# INA219x4_DoubleWing.net
KiCad netlist of a schematic drawn in EAGLE
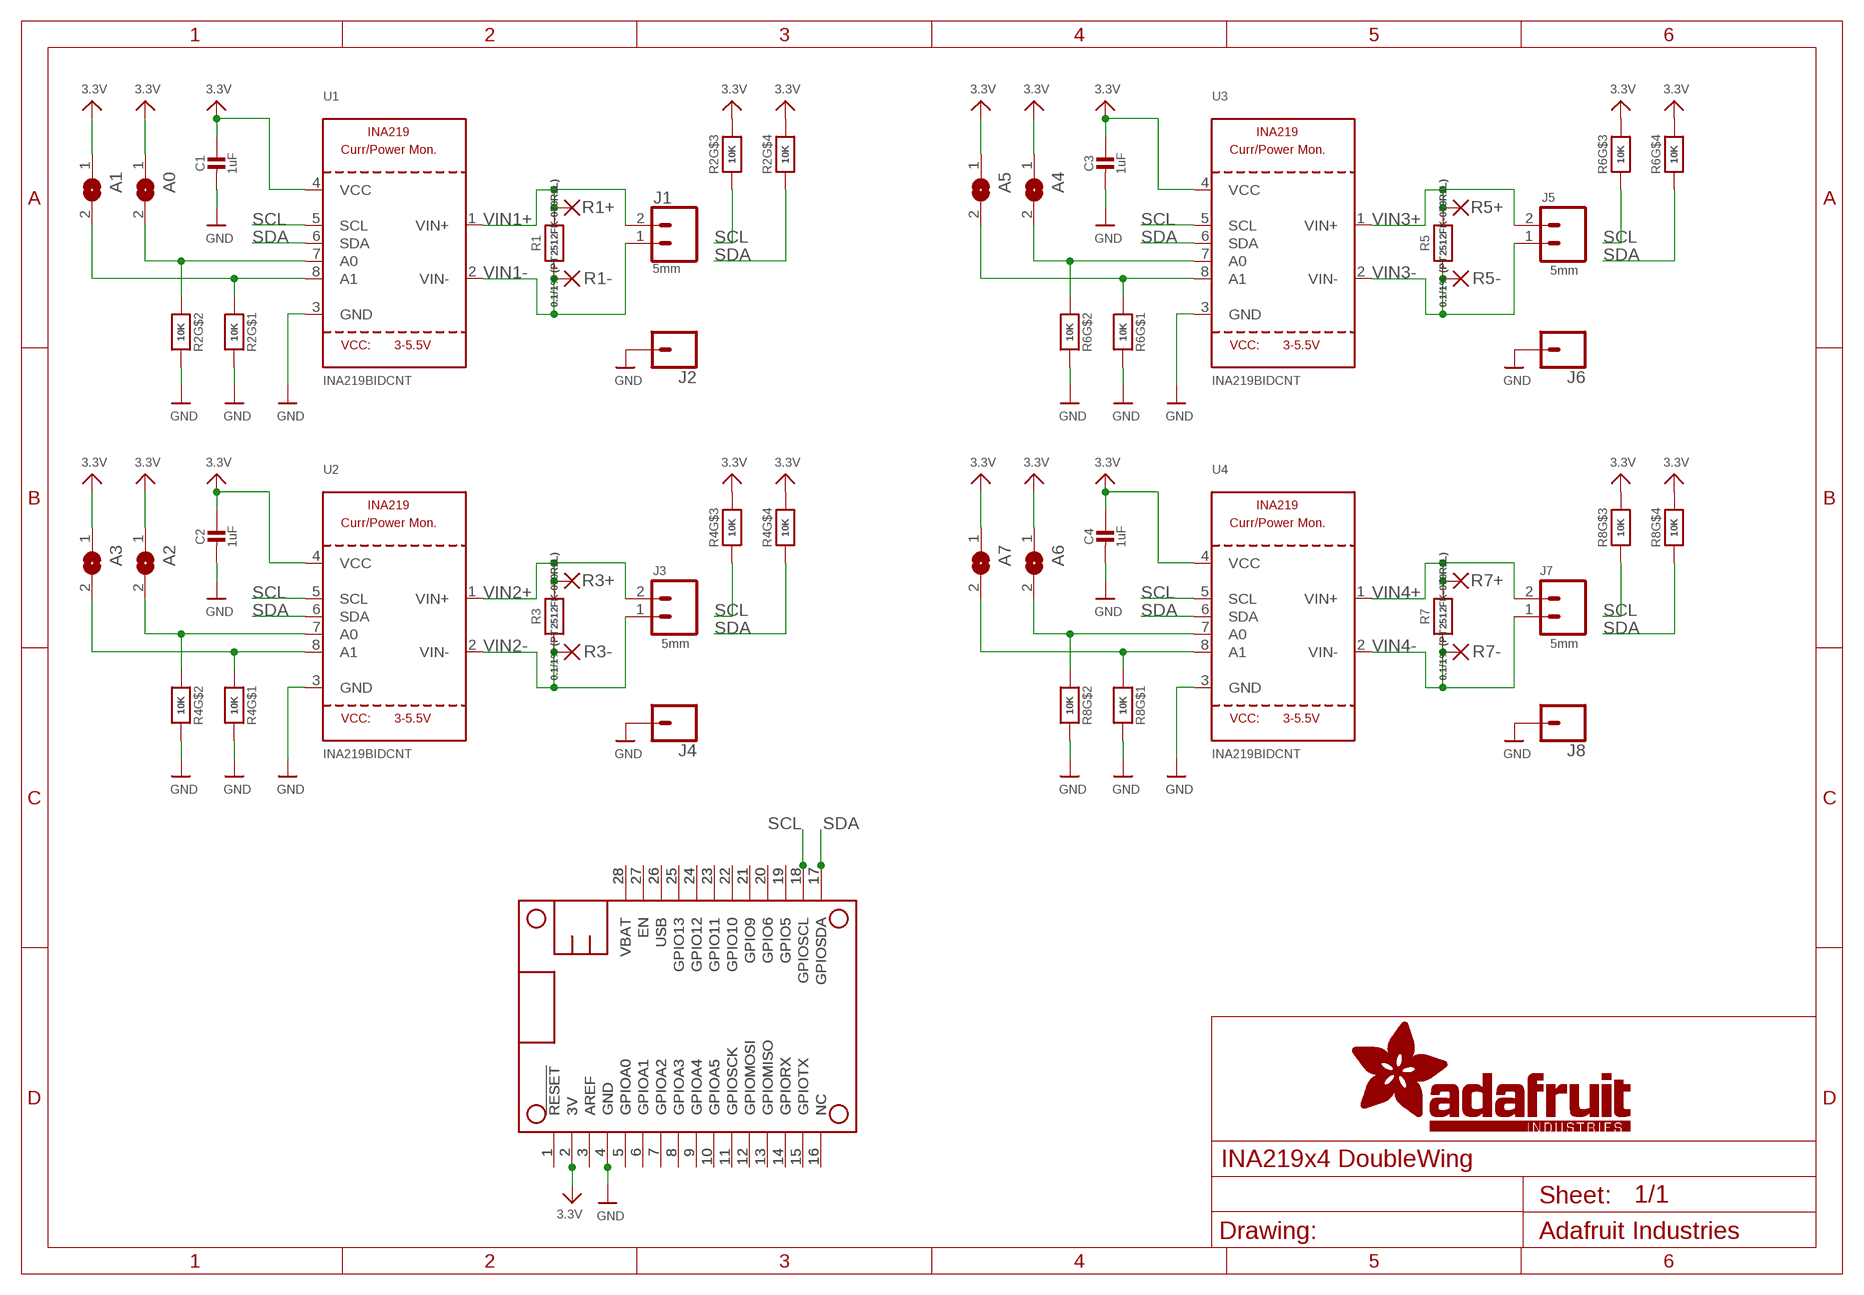
[diagram p0: schematic, sheet 1]

(export (version "E")
  (design (tool "Eeschema 10.0.6"))
  (components
    (comp (ref "A0")
      (value "SOLDERJUMPERREFLOW_NOPASTE")
      (footprint "eagle-import:SOLDERJUMPER_REFLOW_NOPASTE")
      (libsource (lib "eagle-import") (part "SOLDERJUMPERREFLOW_NOPASTE"))
    )
    (comp (ref "A1")
      (value "SOLDERJUMPERREFLOW_NOPASTE")
      (footprint "eagle-import:SOLDERJUMPER_REFLOW_NOPASTE")
      (libsource (lib "eagle-import") (part "SOLDERJUMPERREFLOW_NOPASTE"))
    )
    (comp (ref "A2")
      (value "SOLDERJUMPERREFLOW_NOPASTE")
      (footprint "eagle-import:SOLDERJUMPER_REFLOW_NOPASTE")
      (libsource (lib "eagle-import") (part "SOLDERJUMPERREFLOW_NOPASTE"))
    )
    (comp (ref "A3")
      (value "SOLDERJUMPERREFLOW_NOPASTE")
      (footprint "eagle-import:SOLDERJUMPER_REFLOW_NOPASTE")
      (libsource (lib "eagle-import") (part "SOLDERJUMPERREFLOW_NOPASTE"))
    )
    (comp (ref "A4")
      (value "SOLDERJUMPERREFLOW_NOPASTE")
      (footprint "eagle-import:SOLDERJUMPER_REFLOW_NOPASTE")
      (libsource (lib "eagle-import") (part "SOLDERJUMPERREFLOW_NOPASTE"))
    )
    (comp (ref "A5")
      (value "SOLDERJUMPERREFLOW_NOPASTE")
      (footprint "eagle-import:SOLDERJUMPER_REFLOW_NOPASTE")
      (libsource (lib "eagle-import") (part "SOLDERJUMPERREFLOW_NOPASTE"))
    )
    (comp (ref "A6")
      (value "SOLDERJUMPERREFLOW_NOPASTE")
      (footprint "eagle-import:SOLDERJUMPER_REFLOW_NOPASTE")
      (libsource (lib "eagle-import") (part "SOLDERJUMPERREFLOW_NOPASTE"))
    )
    (comp (ref "A7")
      (value "SOLDERJUMPERREFLOW_NOPASTE")
      (footprint "eagle-import:SOLDERJUMPER_REFLOW_NOPASTE")
      (libsource (lib "eagle-import") (part "SOLDERJUMPERREFLOW_NOPASTE"))
    )
    (comp (ref "C1")
      (value "1uF")
      (footprint "eagle-import:0805-NO@1")
      (libsource (lib "eagle-import") (part "CAP_CERAMIC0805-NOOUTLINE"))
    )
    (comp (ref "C2")
      (value "1uF")
      (footprint "eagle-import:0805-NO@1")
      (libsource (lib "eagle-import") (part "CAP_CERAMIC0805-NOOUTLINE"))
    )
    (comp (ref "C3")
      (value "1uF")
      (footprint "eagle-import:0805-NO@1")
      (libsource (lib "eagle-import") (part "CAP_CERAMIC0805-NOOUTLINE"))
    )
    (comp (ref "C4")
      (value "1uF")
      (footprint "eagle-import:0805-NO@1")
      (libsource (lib "eagle-import") (part "CAP_CERAMIC0805-NOOUTLINE"))
    )
    (comp (ref "J1")
      (value "5mm")
      (footprint "eagle-import:SCREWTERMINAL-5MM-2")
      (libsource (lib "eagle-import") (part "CONN_025MM"))
    )
    (comp (ref "J2")
      (value "CONN_01")
      (footprint "eagle-import:1X01")
      (libsource (lib "eagle-import") (part "CONN_01"))
    )
    (comp (ref "J3")
      (value "5mm")
      (footprint "eagle-import:SCREWTERMINAL-5MM-2")
      (libsource (lib "eagle-import") (part "CONN_025MM"))
    )
    (comp (ref "J4")
      (value "CONN_01")
      (footprint "eagle-import:1X01")
      (libsource (lib "eagle-import") (part "CONN_01"))
    )
    (comp (ref "J5")
      (value "5mm")
      (footprint "eagle-import:SCREWTERMINAL-5MM-2")
      (libsource (lib "eagle-import") (part "CONN_025MM"))
    )
    (comp (ref "J6")
      (value "CONN_01")
      (footprint "eagle-import:1X01")
      (libsource (lib "eagle-import") (part "CONN_01"))
    )
    (comp (ref "J7")
      (value "5mm")
      (footprint "eagle-import:SCREWTERMINAL-5MM-2")
      (libsource (lib "eagle-import") (part "CONN_025MM"))
    )
    (comp (ref "J8")
      (value "CONN_01")
      (footprint "eagle-import:1X01")
      (libsource (lib "eagle-import") (part "CONN_01"))
    )
    (comp (ref "MS1")
      (value "FEATHERWING_NODIM")
      (footprint "eagle-import:FEATHERWING_DIM")
      (libsource (lib "eagle-import") (part "FEATHERWING_NODIM"))
    )
    (comp (ref "MS2")
      (value "FEATHERWING_NODIM")
      (footprint "eagle-import:FEATHERWING_DIM")
      (libsource (lib "eagle-import") (part "FEATHERWING_NODIM"))
    )
    (comp (ref "R1")
      (value "0.1/1% (PT2512FK-070R1L)")
      (footprint "eagle-import:2512")
      (libsource (lib "eagle-import") (part "RESISTOR2512"))
    )
    (comp (ref "R1+")
      (value "1,6/0,9")
      (footprint "eagle-import:1,6_0,9")
      (libsource (lib "eagle-import") (part "1,6/0,9"))
    )
    (comp (ref "R1-")
      (value "1,6/0,9")
      (footprint "eagle-import:1,6_0,9")
      (libsource (lib "eagle-import") (part "1,6/0,9"))
    )
    (comp (ref "R2")
      (value "10K")
      (footprint "eagle-import:RESPACK_4X0603")
      (libsource (lib "eagle-import") (part "RESISTOR_4PACK"))
    )
    (comp (ref "R3")
      (value "0.1/1% (PT2512FK-070R1L)")
      (footprint "eagle-import:2512")
      (libsource (lib "eagle-import") (part "RESISTOR2512"))
    )
    (comp (ref "R3+")
      (value "1,6/0,9")
      (footprint "eagle-import:1,6_0,9")
      (libsource (lib "eagle-import") (part "1,6/0,9"))
    )
    (comp (ref "R3-")
      (value "1,6/0,9")
      (footprint "eagle-import:1,6_0,9")
      (libsource (lib "eagle-import") (part "1,6/0,9"))
    )
    (comp (ref "R4")
      (value "10K")
      (footprint "eagle-import:RESPACK_4X0603")
      (libsource (lib "eagle-import") (part "RESISTOR_4PACK"))
    )
    (comp (ref "R5")
      (value "0.1/1% (PT2512FK-070R1L)")
      (footprint "eagle-import:2512")
      (libsource (lib "eagle-import") (part "RESISTOR2512"))
    )
    (comp (ref "R5+")
      (value "1,6/0,9")
      (footprint "eagle-import:1,6_0,9")
      (libsource (lib "eagle-import") (part "1,6/0,9"))
    )
    (comp (ref "R5-")
      (value "1,6/0,9")
      (footprint "eagle-import:1,6_0,9")
      (libsource (lib "eagle-import") (part "1,6/0,9"))
    )
    (comp (ref "R6")
      (value "10K")
      (footprint "eagle-import:RESPACK_4X0603")
      (libsource (lib "eagle-import") (part "RESISTOR_4PACK"))
    )
    (comp (ref "R7")
      (value "0.1/1% (PT2512FK-070R1L)")
      (footprint "eagle-import:2512")
      (libsource (lib "eagle-import") (part "RESISTOR2512"))
    )
    (comp (ref "R7+")
      (value "1,6/0,9")
      (footprint "eagle-import:1,6_0,9")
      (libsource (lib "eagle-import") (part "1,6/0,9"))
    )
    (comp (ref "R7-")
      (value "1,6/0,9")
      (footprint "eagle-import:1,6_0,9")
      (libsource (lib "eagle-import") (part "1,6/0,9"))
    )
    (comp (ref "R8")
      (value "10K")
      (footprint "eagle-import:RESPACK_4X0603")
      (libsource (lib "eagle-import") (part "RESISTOR_4PACK"))
    )
    (comp (ref "U1")
      (value "INA219BIDCNT")
      (footprint "eagle-import:SOT23-8")
      (libsource (lib "eagle-import") (part "INA219"))
    )
    (comp (ref "U2")
      (value "INA219BIDCNT")
      (footprint "eagle-import:SOT23-8")
      (libsource (lib "eagle-import") (part "INA219"))
    )
    (comp (ref "U3")
      (value "INA219BIDCNT")
      (footprint "eagle-import:SOT23-8")
      (libsource (lib "eagle-import") (part "INA219"))
    )
    (comp (ref "U4")
      (value "INA219BIDCNT")
      (footprint "eagle-import:SOT23-8")
      (libsource (lib "eagle-import") (part "INA219"))
    )
  )
  (nets
    (net (code "1") (name "/SCL") (class "Default")
      (node (ref "MS1") (pin "18") (pinfunction "GPIOSCL_18") (pintype "bidirectional"))
      (node (ref "MS2") (pin "18") (pinfunction "GPIOSCL_18") (pintype "bidirectional"))
      (node (ref "R2") (pin "3") (pinfunction "1_3") (pintype "passive"))
      (node (ref "R4") (pin "3") (pinfunction "1_3") (pintype "passive"))
      (node (ref "R6") (pin "3") (pinfunction "1_3") (pintype "passive"))
      (node (ref "R8") (pin "3") (pinfunction "1_3") (pintype "passive"))
      (node (ref "U1") (pin "5") (pinfunction "SCL_5") (pintype "bidirectional"))
      (node (ref "U2") (pin "5") (pinfunction "SCL_5") (pintype "bidirectional"))
      (node (ref "U3") (pin "5") (pinfunction "SCL_5") (pintype "bidirectional"))
      (node (ref "U4") (pin "5") (pinfunction "SCL_5") (pintype "bidirectional"))
    )
    (net (code "2") (name "/SDA") (class "Default")
      (node (ref "MS1") (pin "17") (pinfunction "GPIOSDA_17") (pintype "bidirectional"))
      (node (ref "MS2") (pin "17") (pinfunction "GPIOSDA_17") (pintype "bidirectional"))
      (node (ref "R2") (pin "4") (pinfunction "1_4") (pintype "passive"))
      (node (ref "R4") (pin "4") (pinfunction "1_4") (pintype "passive"))
      (node (ref "R6") (pin "4") (pinfunction "1_4") (pintype "passive"))
      (node (ref "R8") (pin "4") (pinfunction "1_4") (pintype "passive"))
      (node (ref "U1") (pin "6") (pinfunction "SDA_6") (pintype "bidirectional"))
      (node (ref "U2") (pin "6") (pinfunction "SDA_6") (pintype "bidirectional"))
      (node (ref "U3") (pin "6") (pinfunction "SDA_6") (pintype "bidirectional"))
      (node (ref "U4") (pin "6") (pinfunction "SDA_6") (pintype "bidirectional"))
    )
    (net (code "3") (name "/VIN1+") (class "Default")
      (node (ref "J1") (pin "2") (pinfunction "2_2") (pintype "passive"))
      (node (ref "R1") (pin "2") (pinfunction "2_2") (pintype "passive"))
      (node (ref "R1+") (pin "1") (pinfunction "P_1") (pintype "passive"))
      (node (ref "U1") (pin "1") (pinfunction "VIN+_1") (pintype "bidirectional"))
    )
    (net (code "4") (name "/VIN1-") (class "Default")
      (node (ref "J1") (pin "1") (pinfunction "1_1") (pintype "passive"))
      (node (ref "R1") (pin "1") (pinfunction "1_1") (pintype "passive"))
      (node (ref "R1-") (pin "1") (pinfunction "P_1") (pintype "passive"))
      (node (ref "U1") (pin "2") (pinfunction "VIN-_2") (pintype "bidirectional"))
    )
    (net (code "5") (name "/VIN2+") (class "Default")
      (node (ref "J3") (pin "2") (pinfunction "2_2") (pintype "passive"))
      (node (ref "R3") (pin "2") (pinfunction "2_2") (pintype "passive"))
      (node (ref "R3+") (pin "1") (pinfunction "P_1") (pintype "passive"))
      (node (ref "U2") (pin "1") (pinfunction "VIN+_1") (pintype "bidirectional"))
    )
    (net (code "6") (name "/VIN2-") (class "Default")
      (node (ref "J3") (pin "1") (pinfunction "1_1") (pintype "passive"))
      (node (ref "R3") (pin "1") (pinfunction "1_1") (pintype "passive"))
      (node (ref "R3-") (pin "1") (pinfunction "P_1") (pintype "passive"))
      (node (ref "U2") (pin "2") (pinfunction "VIN-_2") (pintype "bidirectional"))
    )
    (net (code "7") (name "/VIN3+") (class "Default")
      (node (ref "J5") (pin "2") (pinfunction "2_2") (pintype "passive"))
      (node (ref "R5") (pin "2") (pinfunction "2_2") (pintype "passive"))
      (node (ref "R5+") (pin "1") (pinfunction "P_1") (pintype "passive"))
      (node (ref "U3") (pin "1") (pinfunction "VIN+_1") (pintype "bidirectional"))
    )
    (net (code "8") (name "/VIN3-") (class "Default")
      (node (ref "J5") (pin "1") (pinfunction "1_1") (pintype "passive"))
      (node (ref "R5") (pin "1") (pinfunction "1_1") (pintype "passive"))
      (node (ref "R5-") (pin "1") (pinfunction "P_1") (pintype "passive"))
      (node (ref "U3") (pin "2") (pinfunction "VIN-_2") (pintype "bidirectional"))
    )
    (net (code "9") (name "/VIN4+") (class "Default")
      (node (ref "J7") (pin "2") (pinfunction "2_2") (pintype "passive"))
      (node (ref "R7") (pin "2") (pinfunction "2_2") (pintype "passive"))
      (node (ref "R7+") (pin "1") (pinfunction "P_1") (pintype "passive"))
      (node (ref "U4") (pin "1") (pinfunction "VIN+_1") (pintype "bidirectional"))
    )
    (net (code "10") (name "/VIN4-") (class "Default")
      (node (ref "J7") (pin "1") (pinfunction "1_1") (pintype "passive"))
      (node (ref "R7") (pin "1") (pinfunction "1_1") (pintype "passive"))
      (node (ref "R7-") (pin "1") (pinfunction "P_1") (pintype "passive"))
      (node (ref "U4") (pin "2") (pinfunction "VIN-_2") (pintype "bidirectional"))
    )
    (net (code "11") (name "3.3V") (class "Default")
      (node (ref "A0") (pin "1") (pinfunction "1_1") (pintype "passive"))
      (node (ref "A1") (pin "1") (pinfunction "1_1") (pintype "passive"))
      (node (ref "A2") (pin "1") (pinfunction "1_1") (pintype "passive"))
      (node (ref "A3") (pin "1") (pinfunction "1_1") (pintype "passive"))
      (node (ref "A4") (pin "1") (pinfunction "1_1") (pintype "passive"))
      (node (ref "A5") (pin "1") (pinfunction "1_1") (pintype "passive"))
      (node (ref "A6") (pin "1") (pinfunction "1_1") (pintype "passive"))
      (node (ref "A7") (pin "1") (pinfunction "1_1") (pintype "passive"))
      (node (ref "C1") (pin "1") (pinfunction "1_1") (pintype "passive"))
      (node (ref "C2") (pin "1") (pinfunction "1_1") (pintype "passive"))
      (node (ref "C3") (pin "1") (pinfunction "1_1") (pintype "passive"))
      (node (ref "C4") (pin "1") (pinfunction "1_1") (pintype "passive"))
      (node (ref "MS1") (pin "2") (pinfunction "3V_2") (pintype "power_in"))
      (node (ref "MS2") (pin "2") (pinfunction "3V_2") (pintype "power_in"))
      (node (ref "R2") (pin "5") (pinfunction "2_5") (pintype "passive"))
      (node (ref "R2") (pin "6") (pinfunction "2_6") (pintype "passive"))
      (node (ref "R4") (pin "5") (pinfunction "2_5") (pintype "passive"))
      (node (ref "R4") (pin "6") (pinfunction "2_6") (pintype "passive"))
      (node (ref "R6") (pin "5") (pinfunction "2_5") (pintype "passive"))
      (node (ref "R6") (pin "6") (pinfunction "2_6") (pintype "passive"))
      (node (ref "R8") (pin "5") (pinfunction "2_5") (pintype "passive"))
      (node (ref "R8") (pin "6") (pinfunction "2_6") (pintype "passive"))
      (node (ref "U1") (pin "4") (pinfunction "VCC_4") (pintype "power_in"))
      (node (ref "U2") (pin "4") (pinfunction "VCC_4") (pintype "power_in"))
      (node (ref "U3") (pin "4") (pinfunction "VCC_4") (pintype "power_in"))
      (node (ref "U4") (pin "4") (pinfunction "VCC_4") (pintype "power_in"))
    )
    (net (code "12") (name "GND") (class "Default")
      (node (ref "C1") (pin "2") (pinfunction "2_2") (pintype "passive"))
      (node (ref "C2") (pin "2") (pinfunction "2_2") (pintype "passive"))
      (node (ref "C3") (pin "2") (pinfunction "2_2") (pintype "passive"))
      (node (ref "C4") (pin "2") (pinfunction "2_2") (pintype "passive"))
      (node (ref "J2") (pin "1") (pinfunction "1_1") (pintype "passive"))
      (node (ref "J4") (pin "1") (pinfunction "1_1") (pintype "passive"))
      (node (ref "J6") (pin "1") (pinfunction "1_1") (pintype "passive"))
      (node (ref "J8") (pin "1") (pinfunction "1_1") (pintype "passive"))
      (node (ref "MS1") (pin "4") (pinfunction "GND_4") (pintype "power_in"))
      (node (ref "MS2") (pin "4") (pinfunction "GND_4") (pintype "power_in"))
      (node (ref "R2") (pin "7") (pinfunction "2_7") (pintype "passive"))
      (node (ref "R2") (pin "8") (pinfunction "2_8") (pintype "passive"))
      (node (ref "R4") (pin "7") (pinfunction "2_7") (pintype "passive"))
      (node (ref "R4") (pin "8") (pinfunction "2_8") (pintype "passive"))
      (node (ref "R6") (pin "7") (pinfunction "2_7") (pintype "passive"))
      (node (ref "R6") (pin "8") (pinfunction "2_8") (pintype "passive"))
      (node (ref "R8") (pin "7") (pinfunction "2_7") (pintype "passive"))
      (node (ref "R8") (pin "8") (pinfunction "2_8") (pintype "passive"))
      (node (ref "U1") (pin "3") (pinfunction "GND_3") (pintype "power_in"))
      (node (ref "U2") (pin "3") (pinfunction "GND_3") (pintype "power_in"))
      (node (ref "U3") (pin "3") (pinfunction "GND_3") (pintype "power_in"))
      (node (ref "U4") (pin "3") (pinfunction "GND_3") (pintype "power_in"))
    )
    (net (code "13") (name "Net-(MS1-AREF)") (class "Default")
      (node (ref "MS1") (pin "3") (pinfunction "AREF_3") (pintype "passive"))
      (node (ref "MS2") (pin "3") (pinfunction "AREF_3") (pintype "passive"))
    )
    (net (code "14") (name "Net-(MS1-EN)") (class "Default")
      (node (ref "MS1") (pin "27") (pinfunction "EN_27") (pintype "passive"))
      (node (ref "MS2") (pin "27") (pinfunction "EN_27") (pintype "passive"))
    )
    (net (code "15") (name "Net-(MS1-GPIO5)") (class "Default")
      (node (ref "MS1") (pin "19") (pinfunction "GPIO5_19") (pintype "bidirectional"))
      (node (ref "MS2") (pin "19") (pinfunction "GPIO5_19") (pintype "bidirectional"))
    )
    (net (code "16") (name "Net-(MS1-GPIO6)") (class "Default")
      (node (ref "MS1") (pin "20") (pinfunction "GPIO6_20") (pintype "bidirectional"))
      (node (ref "MS2") (pin "20") (pinfunction "GPIO6_20") (pintype "bidirectional"))
    )
    (net (code "17") (name "Net-(MS1-GPIO9)") (class "Default")
      (node (ref "MS1") (pin "21") (pinfunction "GPIO9_21") (pintype "bidirectional"))
      (node (ref "MS2") (pin "21") (pinfunction "GPIO9_21") (pintype "bidirectional"))
    )
    (net (code "18") (name "Net-(MS1-GPIO10)") (class "Default")
      (node (ref "MS1") (pin "22") (pinfunction "GPIO10_22") (pintype "bidirectional"))
      (node (ref "MS2") (pin "22") (pinfunction "GPIO10_22") (pintype "bidirectional"))
    )
    (net (code "19") (name "Net-(MS1-GPIO11)") (class "Default")
      (node (ref "MS1") (pin "23") (pinfunction "GPIO11_23") (pintype "bidirectional"))
      (node (ref "MS2") (pin "23") (pinfunction "GPIO11_23") (pintype "bidirectional"))
    )
    (net (code "20") (name "Net-(MS1-GPIO12)") (class "Default")
      (node (ref "MS1") (pin "24") (pinfunction "GPIO12_24") (pintype "bidirectional"))
      (node (ref "MS2") (pin "24") (pinfunction "GPIO12_24") (pintype "bidirectional"))
    )
    (net (code "21") (name "Net-(MS1-GPIO13)") (class "Default")
      (node (ref "MS1") (pin "25") (pinfunction "GPIO13_25") (pintype "bidirectional"))
      (node (ref "MS2") (pin "25") (pinfunction "GPIO13_25") (pintype "bidirectional"))
    )
    (net (code "22") (name "Net-(MS1-GPIOA0)") (class "Default")
      (node (ref "MS1") (pin "5") (pinfunction "GPIOA0_5") (pintype "bidirectional"))
      (node (ref "MS2") (pin "5") (pinfunction "GPIOA0_5") (pintype "bidirectional"))
    )
    (net (code "23") (name "Net-(MS1-GPIOA1)") (class "Default")
      (node (ref "MS1") (pin "6") (pinfunction "GPIOA1_6") (pintype "bidirectional"))
      (node (ref "MS2") (pin "6") (pinfunction "GPIOA1_6") (pintype "bidirectional"))
    )
    (net (code "24") (name "Net-(MS1-GPIOA2)") (class "Default")
      (node (ref "MS1") (pin "7") (pinfunction "GPIOA2_7") (pintype "bidirectional"))
      (node (ref "MS2") (pin "7") (pinfunction "GPIOA2_7") (pintype "bidirectional"))
    )
    (net (code "25") (name "Net-(MS1-GPIOA3)") (class "Default")
      (node (ref "MS1") (pin "8") (pinfunction "GPIOA3_8") (pintype "bidirectional"))
      (node (ref "MS2") (pin "8") (pinfunction "GPIOA3_8") (pintype "bidirectional"))
    )
    (net (code "26") (name "Net-(MS1-GPIOA4)") (class "Default")
      (node (ref "MS1") (pin "9") (pinfunction "GPIOA4_9") (pintype "bidirectional"))
      (node (ref "MS2") (pin "9") (pinfunction "GPIOA4_9") (pintype "bidirectional"))
    )
    (net (code "27") (name "Net-(MS1-GPIOA5)") (class "Default")
      (node (ref "MS1") (pin "10") (pinfunction "GPIOA5_10") (pintype "bidirectional"))
      (node (ref "MS2") (pin "10") (pinfunction "GPIOA5_10") (pintype "bidirectional"))
    )
    (net (code "28") (name "Net-(MS1-GPIOMISO)") (class "Default")
      (node (ref "MS1") (pin "13") (pinfunction "GPIOMISO_13") (pintype "bidirectional"))
      (node (ref "MS2") (pin "13") (pinfunction "GPIOMISO_13") (pintype "bidirectional"))
    )
    (net (code "29") (name "Net-(MS1-GPIOMOSI)") (class "Default")
      (node (ref "MS1") (pin "12") (pinfunction "GPIOMOSI_12") (pintype "bidirectional"))
      (node (ref "MS2") (pin "12") (pinfunction "GPIOMOSI_12") (pintype "bidirectional"))
    )
    (net (code "30") (name "Net-(MS1-GPIORX)") (class "Default")
      (node (ref "MS1") (pin "14") (pinfunction "GPIORX_14") (pintype "bidirectional"))
      (node (ref "MS2") (pin "14") (pinfunction "GPIORX_14") (pintype "bidirectional"))
    )
    (net (code "31") (name "Net-(MS1-GPIOSCK)") (class "Default")
      (node (ref "MS1") (pin "11") (pinfunction "GPIOSCK_11") (pintype "bidirectional"))
      (node (ref "MS2") (pin "11") (pinfunction "GPIOSCK_11") (pintype "bidirectional"))
    )
    (net (code "32") (name "Net-(MS1-GPIOTX)") (class "Default")
      (node (ref "MS1") (pin "15") (pinfunction "GPIOTX_15") (pintype "bidirectional"))
      (node (ref "MS2") (pin "15") (pinfunction "GPIOTX_15") (pintype "bidirectional"))
    )
    (net (code "33") (name "Net-(MS1-NC)") (class "Default")
      (node (ref "MS1") (pin "16") (pinfunction "NC_16") (pintype "passive"))
      (node (ref "MS2") (pin "16") (pinfunction "NC_16") (pintype "passive"))
    )
    (net (code "34") (name "Net-(MS1-USB)") (class "Default")
      (node (ref "MS1") (pin "26") (pinfunction "USB_26") (pintype "power_in"))
      (node (ref "MS2") (pin "26") (pinfunction "USB_26") (pintype "power_in"))
    )
    (net (code "35") (name "Net-(MS1-VBAT)") (class "Default")
      (node (ref "MS1") (pin "28") (pinfunction "VBAT_28") (pintype "power_in"))
      (node (ref "MS2") (pin "28") (pinfunction "VBAT_28") (pintype "power_in"))
    )
    (net (code "36") (name "Net-(MS1-~{RESET})") (class "Default")
      (node (ref "MS1") (pin "1") (pinfunction "~{RESET}_1") (pintype "input"))
      (node (ref "MS2") (pin "1") (pinfunction "~{RESET}_1") (pintype "input"))
    )
    (net (code "37") (name "Net-(R2B-1)") (class "Default")
      (node (ref "A0") (pin "2") (pinfunction "2_2") (pintype "passive"))
      (node (ref "R2") (pin "2") (pinfunction "1_2") (pintype "passive"))
      (node (ref "U1") (pin "7") (pinfunction "A0_7") (pintype "bidirectional"))
    )
    (net (code "38") (name "Net-(R4B-1)") (class "Default")
      (node (ref "A2") (pin "2") (pinfunction "2_2") (pintype "passive"))
      (node (ref "R4") (pin "2") (pinfunction "1_2") (pintype "passive"))
      (node (ref "U2") (pin "7") (pinfunction "A0_7") (pintype "bidirectional"))
    )
    (net (code "39") (name "Net-(R6B-1)") (class "Default")
      (node (ref "A4") (pin "2") (pinfunction "2_2") (pintype "passive"))
      (node (ref "R6") (pin "2") (pinfunction "1_2") (pintype "passive"))
      (node (ref "U3") (pin "7") (pinfunction "A0_7") (pintype "bidirectional"))
    )
    (net (code "40") (name "Net-(R8B-1)") (class "Default")
      (node (ref "A6") (pin "2") (pinfunction "2_2") (pintype "passive"))
      (node (ref "R8") (pin "2") (pinfunction "1_2") (pintype "passive"))
      (node (ref "U4") (pin "7") (pinfunction "A0_7") (pintype "bidirectional"))
    )
    (net (code "41") (name "Net-(U1-A1)") (class "Default")
      (node (ref "A1") (pin "2") (pinfunction "2_2") (pintype "passive"))
      (node (ref "R2") (pin "1") (pinfunction "1_1") (pintype "passive"))
      (node (ref "U1") (pin "8") (pinfunction "A1_8") (pintype "bidirectional"))
    )
    (net (code "42") (name "Net-(U2-A1)") (class "Default")
      (node (ref "A3") (pin "2") (pinfunction "2_2") (pintype "passive"))
      (node (ref "R4") (pin "1") (pinfunction "1_1") (pintype "passive"))
      (node (ref "U2") (pin "8") (pinfunction "A1_8") (pintype "bidirectional"))
    )
    (net (code "43") (name "Net-(U3-A1)") (class "Default")
      (node (ref "A5") (pin "2") (pinfunction "2_2") (pintype "passive"))
      (node (ref "R6") (pin "1") (pinfunction "1_1") (pintype "passive"))
      (node (ref "U3") (pin "8") (pinfunction "A1_8") (pintype "bidirectional"))
    )
    (net (code "44") (name "Net-(U4-A1)") (class "Default")
      (node (ref "A7") (pin "2") (pinfunction "2_2") (pintype "passive"))
      (node (ref "R8") (pin "1") (pinfunction "1_1") (pintype "passive"))
      (node (ref "U4") (pin "8") (pinfunction "A1_8") (pintype "bidirectional"))
    )
  )
)
